# AuxiliaryPowerSupply.net
KiCad netlist of a schematic drawn in Altium Designer
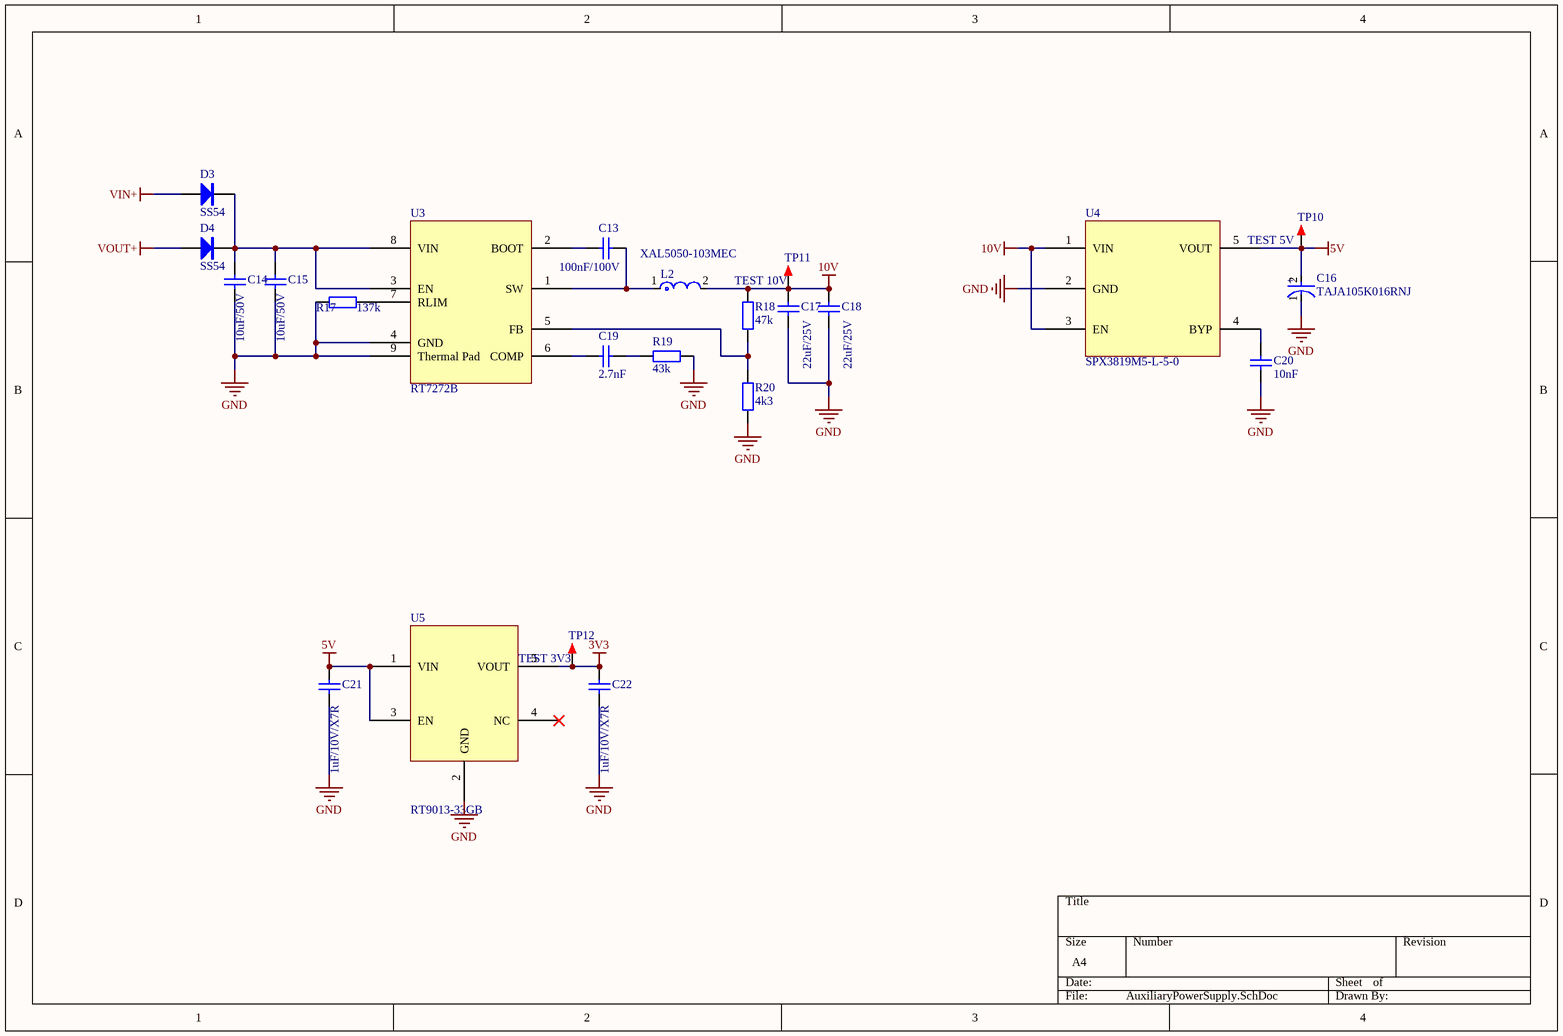
[diagram p0: AuxiliaryPowerSupply.SchDoc]

(export (version "E")
  (design (tool "Eeschema 10.0.6"))
  (components
    (comp (ref "C13")
      (value "100nF/100V")
      (footprint "C0402_L")
      (description "贴片电容")
      (libsource (lib "0.1 - 电阻-电容-电感-晶振-晶体-磁珠-电位器") (part "C"))
    )
    (comp (ref "C14")
      (value "10uF/50V")
      (footprint "C1206_L")
      (description "贴片电容")
      (libsource (lib "0.1 - 电阻-电容-电感-晶振-晶体-磁珠-电位器") (part "C"))
    )
    (comp (ref "C15")
      (value "10uF/50V")
      (footprint "C1206_L")
      (description "贴片电容")
      (libsource (lib "0.1 - 电阻-电容-电感-晶振-晶体-磁珠-电位器") (part "C"))
    )
    (comp (ref "C16")
      (value "TAJA105K016RNJ")
      (footprint "FP-TAJA-MFG")
      (description "CAP TANT 1UF 10% 16V 1206")
      (fields (field (name "TOLERANCE") "20%") (field (name "VOLTAGE") "16V"))
      (libsource (lib "Altium Content Vault") (part "203bc49f2ac43e59fd269a8c329ed05"))
    )
    (comp (ref "C17")
      (value "22uF/25V")
      (footprint "C0805_L")
      (description "贴片电容")
      (libsource (lib "0.1 - 电阻-电容-电感-晶振-晶体-磁珠-电位器") (part "C"))
    )
    (comp (ref "C18")
      (value "22uF/25V")
      (footprint "C0805_L")
      (description "贴片电容")
      (libsource (lib "0.1 - 电阻-电容-电感-晶振-晶体-磁珠-电位器") (part "C"))
    )
    (comp (ref "C19")
      (value "2.7nF")
      (footprint "C0402_L")
      (description "贴片电容")
      (libsource (lib "0.1 - 电阻-电容-电感-晶振-晶体-磁珠-电位器") (part "C"))
    )
    (comp (ref "C20")
      (value "10nF")
      (footprint "C0402_L")
      (description "贴片电容")
      (libsource (lib "0.1 - 电阻-电容-电感-晶振-晶体-磁珠-电位器") (part "C"))
    )
    (comp (ref "C21")
      (value "1uF/10V/X7R")
      (footprint "C0402_L")
      (description "贴片电容")
      (libsource (lib "0.1 - 电阻-电容-电感-晶振-晶体-磁珠-电位器") (part "C"))
    )
    (comp (ref "C22")
      (value "1uF/10V/X7R")
      (footprint "C0402_L")
      (description "贴片电容")
      (libsource (lib "0.1 - 电阻-电容-电感-晶振-晶体-磁珠-电位器") (part "C"))
    )
    (comp (ref "D3")
      (value "SS54")
      (footprint "SMA")
      (description "肖特基二极管")
      (fields (field (name "版权归属") "源创客"))
      (libsource (lib "源创客") (part "SS14"))
    )
    (comp (ref "D4")
      (value "SS54")
      (footprint "SMA")
      (description "肖特基二极管")
      (fields (field (name "版权归属") "源创客"))
      (libsource (lib "源创客") (part "SS14"))
    )
    (comp (ref "L2")
      (value "XAL5050-103MEC")
      (footprint "FP-XAL5050-MFG")
      (description "Shielded Power Inductors 10uH 20% 4.9A 45mOhm")
      (fields (field (name "TOLERANCE") "20%"))
      (libsource (lib "Altium Content Vault") (part "4cc4b267dca4c8e51f7102f422741d8"))
    )
    (comp (ref "R17")
      (value "137k")
      (footprint "R0402_L")
      (description "贴片电阻")
      (libsource (lib "0.1 - 电阻-电容-电感-晶振-晶体-磁珠-电位器") (part "R"))
    )
    (comp (ref "R18")
      (value "47k")
      (footprint "R0402_L")
      (description "贴片电阻")
      (libsource (lib "0.1 - 电阻-电容-电感-晶振-晶体-磁珠-电位器") (part "R"))
    )
    (comp (ref "R19")
      (value "43k")
      (footprint "R0402_L")
      (description "贴片电阻")
      (libsource (lib "0.1 - 电阻-电容-电感-晶振-晶体-磁珠-电位器") (part "R"))
    )
    (comp (ref "R20")
      (value "4k3")
      (footprint "R0402_L")
      (description "贴片电阻")
      (libsource (lib "0.1 - 电阻-电容-电感-晶振-晶体-磁珠-电位器") (part "R"))
    )
    (comp (ref "TP10")
      (value "TEST 5V")
      (footprint "TEST TP1.4_W")
      (description "测试环")
      (libsource (lib "0.5 - 按键-开关-蜂鸣器-保险丝-电池-测试点-Mark点") (part "TEST TP"))
    )
    (comp (ref "TP11")
      (value "TEST 10V")
      (footprint "TEST TP1.4_W")
      (description "测试环")
      (libsource (lib "0.5 - 按键-开关-蜂鸣器-保险丝-电池-测试点-Mark点") (part "TEST TP"))
    )
    (comp (ref "TP12")
      (value "TEST 3V3")
      (footprint "TEST TP1.4_W")
      (description "测试环")
      (libsource (lib "0.5 - 按键-开关-蜂鸣器-保险丝-电池-测试点-Mark点") (part "TEST TP"))
    )
    (comp (ref "U3")
      (value "RT7272B")
      (footprint "RT7272B")
      (libsource (lib "DigitalBuckBoost") (part "RT7272B"))
    )
    (comp (ref "U4")
      (value "SPX3819M5-L-5-0")
      (footprint "SPX3819M5-L-5-0")
      (libsource (lib "DigitalBuckBoost") (part "SPX3819M5-L-5-0"))
    )
    (comp (ref "U5")
      (value "RT9013-33GB")
      (footprint "RT9013-33GB")
      (libsource (lib "DigitalBuckBoost") (part "RT9013-33GB"))
    )
  )
  (nets
    (net (code "1") (name "3V3") (class "Default")
      (node (ref "C22") (pin "2") (pinfunction "2_2") (pintype "passive"))
      (node (ref "TP12") (pin "1") (pinfunction "1_1") (pintype "passive"))
      (node (ref "U5") (pin "5") (pinfunction "VOUT_5") (pintype "passive"))
    )
    (net (code "2") (name "5V") (class "Default")
      (node (ref "C16") (pin "2") (pinfunction "A_2") (pintype "passive"))
      (node (ref "C21") (pin "2") (pinfunction "2_2") (pintype "passive"))
      (node (ref "TP10") (pin "1") (pinfunction "1_1") (pintype "passive"))
      (node (ref "U4") (pin "5") (pinfunction "VOUT_5") (pintype "passive"))
      (node (ref "U5") (pin "1") (pinfunction "VIN_1") (pintype "passive"))
      (node (ref "U5") (pin "3") (pinfunction "EN_3") (pintype "passive"))
    )
    (net (code "3") (name "10V") (class "Default")
      (node (ref "C17") (pin "2") (pinfunction "2_2") (pintype "passive"))
      (node (ref "C18") (pin "2") (pinfunction "2_2") (pintype "passive"))
      (node (ref "L2") (pin "2") (pinfunction "2_2") (pintype "passive"))
      (node (ref "R18") (pin "1") (pinfunction "1_1") (pintype "passive"))
      (node (ref "TP11") (pin "1") (pinfunction "1_1") (pintype "passive"))
      (node (ref "U4") (pin "1") (pinfunction "VIN_1") (pintype "passive"))
      (node (ref "U4") (pin "3") (pinfunction "EN_3") (pintype "passive"))
    )
    (net (code "4") (name "GND") (class "Default")
      (node (ref "C14") (pin "1") (pinfunction "1_1") (pintype "passive"))
      (node (ref "C15") (pin "1") (pinfunction "1_1") (pintype "passive"))
      (node (ref "C16") (pin "1") (pinfunction "C_1") (pintype "passive"))
      (node (ref "C17") (pin "1") (pinfunction "1_1") (pintype "passive"))
      (node (ref "C18") (pin "1") (pinfunction "1_1") (pintype "passive"))
      (node (ref "C20") (pin "2") (pinfunction "2_2") (pintype "passive"))
      (node (ref "C21") (pin "1") (pinfunction "1_1") (pintype "passive"))
      (node (ref "C22") (pin "1") (pinfunction "1_1") (pintype "passive"))
      (node (ref "R17") (pin "1") (pinfunction "1_1") (pintype "passive"))
      (node (ref "R19") (pin "1") (pinfunction "1_1") (pintype "passive"))
      (node (ref "R20") (pin "1") (pinfunction "1_1") (pintype "passive"))
      (node (ref "U3") (pin "4") (pinfunction "GND_4") (pintype "passive"))
      (node (ref "U3") (pin "9") (pinfunction "Thermal_Pad_9") (pintype "passive"))
      (node (ref "U4") (pin "2") (pinfunction "GND_2") (pintype "passive"))
      (node (ref "U5") (pin "2") (pinfunction "GND_2") (pintype "passive"))
    )
    (net (code "5") (name "Net-(C19-Pad1)") (class "Default")
      (node (ref "C19") (pin "1") (pinfunction "1_1") (pintype "passive"))
      (node (ref "R19") (pin "2") (pinfunction "2_2") (pintype "passive"))
    )
    (net (code "6") (name "Net-(D3-K)") (class "Default")
      (node (ref "C14") (pin "2") (pinfunction "2_2") (pintype "passive"))
      (node (ref "C15") (pin "2") (pinfunction "2_2") (pintype "passive"))
      (node (ref "D3") (pin "2") (pinfunction "K_2") (pintype "passive"))
      (node (ref "D4") (pin "2") (pinfunction "K_2") (pintype "passive"))
      (node (ref "U3") (pin "3") (pinfunction "EN_3") (pintype "passive"))
      (node (ref "U3") (pin "8") (pinfunction "VIN_8") (pintype "passive"))
    )
    (net (code "7") (name "Net-(U3-BOOT)") (class "Default")
      (node (ref "C13") (pin "2") (pinfunction "2_2") (pintype "passive"))
      (node (ref "U3") (pin "2") (pinfunction "BOOT_2") (pintype "passive"))
    )
    (net (code "8") (name "Net-(U3-COMP)") (class "Default")
      (node (ref "C19") (pin "2") (pinfunction "2_2") (pintype "passive"))
      (node (ref "U3") (pin "6") (pinfunction "COMP_6") (pintype "passive"))
    )
    (net (code "9") (name "Net-(U3-FB)") (class "Default")
      (node (ref "R18") (pin "2") (pinfunction "2_2") (pintype "passive"))
      (node (ref "R20") (pin "2") (pinfunction "2_2") (pintype "passive"))
      (node (ref "U3") (pin "5") (pinfunction "FB_5") (pintype "passive"))
    )
    (net (code "10") (name "Net-(U3-RLIM)") (class "Default")
      (node (ref "R17") (pin "2") (pinfunction "2_2") (pintype "passive"))
      (node (ref "U3") (pin "7") (pinfunction "RLIM_7") (pintype "passive"))
    )
    (net (code "11") (name "Net-(U3-SW)") (class "Default")
      (node (ref "C13") (pin "1") (pinfunction "1_1") (pintype "passive"))
      (node (ref "L2") (pin "1") (pinfunction "1_1") (pintype "passive"))
      (node (ref "U3") (pin "1") (pinfunction "SW_1") (pintype "passive"))
    )
    (net (code "12") (name "Net-(U4-BYP)") (class "Default")
      (node (ref "C20") (pin "1") (pinfunction "1_1") (pintype "passive"))
      (node (ref "U4") (pin "4") (pinfunction "BYP_4") (pintype "passive"))
    )
    (net (code "13") (name "VIN+") (class "Default")
      (node (ref "D3") (pin "1") (pinfunction "A_1") (pintype "passive"))
    )
    (net (code "14") (name "VOUT+") (class "Default")
      (node (ref "D4") (pin "1") (pinfunction "A_1") (pintype "passive"))
    )
    (net (code "15") (name "unconnected-(U5-NC-Pad4)") (class "Default")
      (node (ref "U5") (pin "4") (pinfunction "NC_4") (pintype "passive+no_connect"))
    )
  )
)
